# mother_board.net
KiCad netlist of a schematic drawn in EAGLE
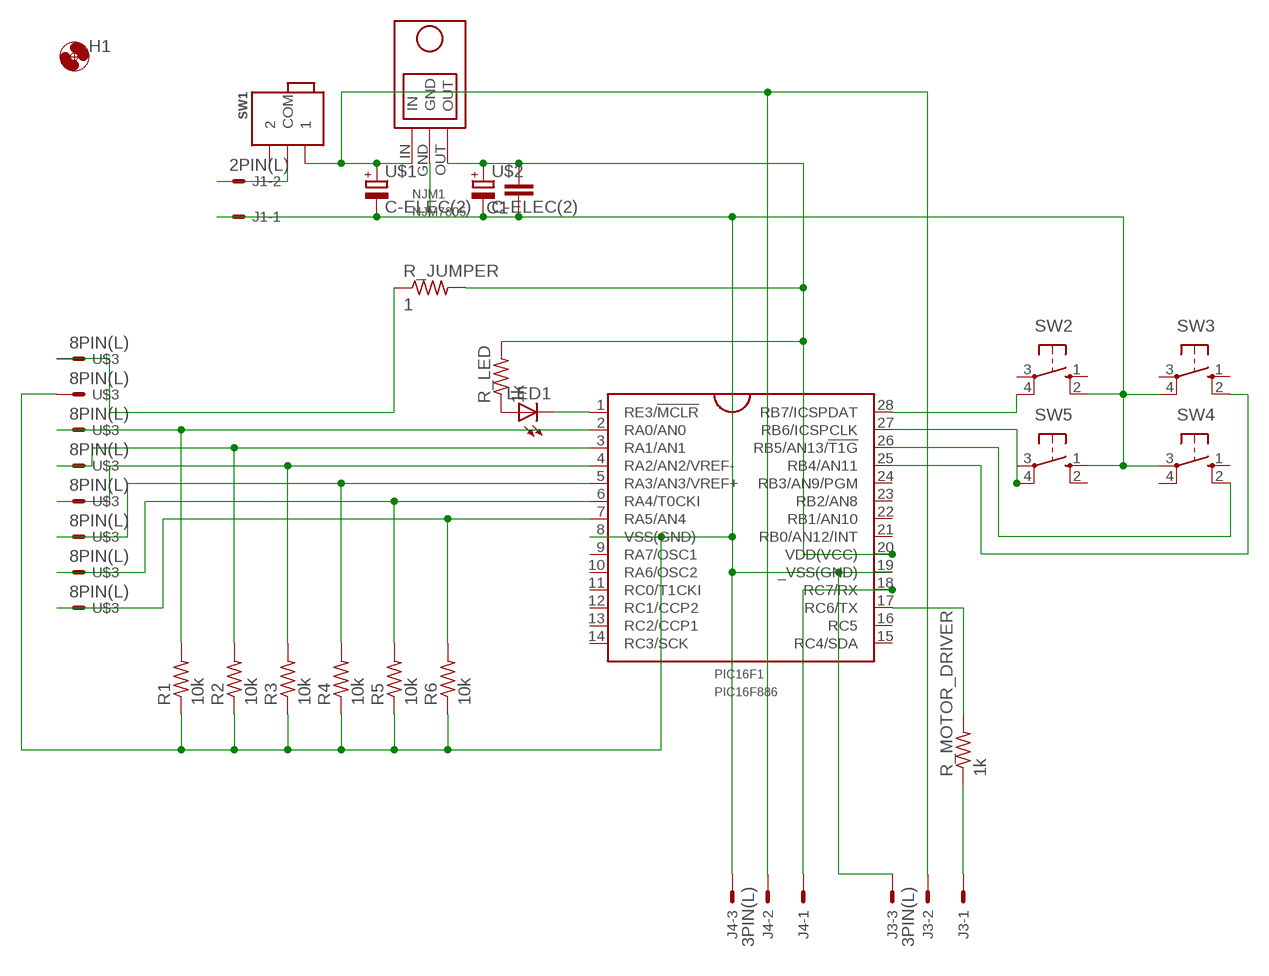
[diagram p0: schematic, sheet 1]

(export (version "E")
  (design (tool "Eeschema 10.0.6"))
  (components
    (comp (ref "C1")
      (value "C-3")
      (footprint "eagle-import:C-3")
      (libsource (lib "eagle-import") (part "C-3"))
    )
    (comp (ref "H1")
      (value "HOLE3.3M3BOLT")
      (footprint "eagle-import:HOLE3.3")
      (libsource (lib "eagle-import") (part "HOLE3.3M3BOLT"))
    )
    (comp (ref "J1")
      (value "2PIN(L)")
      (footprint "eagle-import:2PL")
      (libsource (lib "eagle-import") (part "2PIN(L)"))
    )
    (comp (ref "J3")
      (value "3PIN(L)")
      (footprint "eagle-import:3PL")
      (libsource (lib "eagle-import") (part "3PIN(L)"))
    )
    (comp (ref "J4")
      (value "3PIN(L)")
      (footprint "eagle-import:3PL")
      (libsource (lib "eagle-import") (part "3PIN(L)"))
    )
    (comp (ref "LED1")
      (value "LED-2")
      (footprint "eagle-import:LED5MM-2")
      (libsource (lib "eagle-import") (part "LED-2"))
    )
    (comp (ref "NJM1")
      (value "NJM7805")
      (footprint "eagle-import:NJM7805")
      (libsource (lib "eagle-import") (part "NJM7805"))
    )
    (comp (ref "PIC16F1")
      (value "PIC16F886")
      (footprint "eagle-import:DIL28-3")
      (libsource (lib "eagle-import") (part "PIC16F886"))
    )
    (comp (ref "R1")
      (value "10k")
      (footprint "eagle-import:0207_10")
      (libsource (lib "eagle-import") (part "R-"))
    )
    (comp (ref "R2")
      (value "10k")
      (footprint "eagle-import:0207_10")
      (libsource (lib "eagle-import") (part "R-"))
    )
    (comp (ref "R3")
      (value "10k")
      (footprint "eagle-import:0207_10")
      (libsource (lib "eagle-import") (part "R-"))
    )
    (comp (ref "R4")
      (value "10k")
      (footprint "eagle-import:0207_10")
      (libsource (lib "eagle-import") (part "R-"))
    )
    (comp (ref "R5")
      (value "10k")
      (footprint "eagle-import:0207_10")
      (libsource (lib "eagle-import") (part "R-"))
    )
    (comp (ref "R6")
      (value "10k")
      (footprint "eagle-import:0207_10")
      (libsource (lib "eagle-import") (part "R-"))
    )
    (comp (ref "R_JUMPER")
      (value "1")
      (footprint "eagle-import:0207_10")
      (libsource (lib "eagle-import") (part "R-"))
    )
    (comp (ref "R_LED")
      (value "1k")
      (footprint "eagle-import:0207_10")
      (libsource (lib "eagle-import") (part "R-"))
    )
    (comp (ref "R_MOTOR_DRIVER")
      (value "1k")
      (footprint "eagle-import:0207_10")
      (libsource (lib "eagle-import") (part "R-"))
    )
    (comp (ref "SW1")
      (value "SWITCH_MININORMAL")
      (footprint "eagle-import:SWITCH_MINI")
      (libsource (lib "eagle-import") (part "SWITCH_MININORMAL"))
    )
    (comp (ref "SW2")
      (value "TACTSW")
      (footprint "eagle-import:TACT")
      (libsource (lib "eagle-import") (part "TACTSW"))
    )
    (comp (ref "SW3")
      (value "TACTSW")
      (footprint "eagle-import:TACT")
      (libsource (lib "eagle-import") (part "TACTSW"))
    )
    (comp (ref "SW4")
      (value "TACTSW")
      (footprint "eagle-import:TACT")
      (libsource (lib "eagle-import") (part "TACTSW"))
    )
    (comp (ref "SW5")
      (value "TACTSW")
      (footprint "eagle-import:TACT")
      (libsource (lib "eagle-import") (part "TACTSW"))
    )
    (comp (ref "U$1")
      (value "C-ELEC(2)")
      (footprint "eagle-import:C-6MM(2)")
      (libsource (lib "eagle-import") (part "C-ELEC(2)"))
    )
    (comp (ref "U$2")
      (value "C-ELEC(2)")
      (footprint "eagle-import:C-6MM(2)")
      (libsource (lib "eagle-import") (part "C-ELEC(2)"))
    )
    (comp (ref "U$3")
      (value "8PIN(L)")
      (footprint "eagle-import:8PL")
      (libsource (lib "eagle-import") (part "8PIN(L)"))
    )
  )
  (nets
    (net (code "1") (name "/9V") (class "Default")
      (node (ref "J1") (pin "2") (pinfunction "S_2") (pintype "passive"))
      (node (ref "J3") (pin "2") (pinfunction "S_2") (pintype "passive"))
      (node (ref "J4") (pin "2") (pinfunction "S_2") (pintype "passive"))
      (node (ref "NJM1") (pin "IN") (pinfunction "IN_IN") (pintype "bidirectional"))
      (node (ref "SW1") (pin "1") (pinfunction "1_1") (pintype "passive"))
      (node (ref "SW1") (pin "COM") (pinfunction "COM_COM") (pintype "passive"))
      (node (ref "U$1") (pin "+") (pinfunction "+_+") (pintype "passive"))
    )
    (net (code "2") (name "Net-(J1A-S)") (class "Default")
      (node (ref "C1") (pin "1") (pinfunction "1_1") (pintype "passive"))
      (node (ref "J1") (pin "1") (pinfunction "S_1") (pintype "passive"))
      (node (ref "J3") (pin "3") (pinfunction "S_3") (pintype "passive"))
      (node (ref "J4") (pin "3") (pinfunction "S_3") (pintype "passive"))
      (node (ref "NJM1") (pin "GND") (pinfunction "GND_GND") (pintype "bidirectional"))
      (node (ref "PIC16F1") (pin "19") (pinfunction "_VSS(GND)_19") (pintype "power_in"))
      (node (ref "PIC16F1") (pin "8") (pinfunction "VSS(GND)_8") (pintype "power_in"))
      (node (ref "R1") (pin "1") (pinfunction "1_1") (pintype "passive"))
      (node (ref "R2") (pin "1") (pinfunction "1_1") (pintype "passive"))
      (node (ref "R3") (pin "1") (pinfunction "1_1") (pintype "passive"))
      (node (ref "R4") (pin "1") (pinfunction "1_1") (pintype "passive"))
      (node (ref "R5") (pin "1") (pinfunction "1_1") (pintype "passive"))
      (node (ref "R6") (pin "1") (pinfunction "1_1") (pintype "passive"))
      (node (ref "SW2") (pin "2") (pinfunction "S1_2") (pintype "passive"))
      (node (ref "SW3") (pin "4") (pinfunction "P1_4") (pintype "passive"))
      (node (ref "SW4") (pin "3") (pinfunction "P_3") (pintype "passive"))
      (node (ref "SW5") (pin "1") (pinfunction "S_1") (pintype "passive"))
      (node (ref "U$1") (pin "-") (pinfunction "-_-") (pintype "passive"))
      (node (ref "U$2") (pin "-") (pinfunction "-_-") (pintype "passive"))
      (node (ref "U$3") (pin "P7") (pinfunction "P7_P7") (pintype "passive"))
    )
    (net (code "3") (name "Net-(J3A-S)") (class "Default")
      (node (ref "J3") (pin "1") (pinfunction "S_1") (pintype "passive"))
      (node (ref "R_MOTOR_DRIVER") (pin "1") (pinfunction "1_1") (pintype "passive"))
    )
    (net (code "4") (name "Net-(J4A-S)") (class "Default")
      (node (ref "J4") (pin "1") (pinfunction "S_1") (pintype "passive"))
      (node (ref "PIC16F1") (pin "18") (pinfunction "RC7/RX_18") (pintype "bidirectional"))
    )
    (net (code "5") (name "Net-(LED1-C)") (class "Default")
      (node (ref "LED1") (pin "K") (pinfunction "C_K") (pintype "passive"))
      (node (ref "PIC16F1") (pin "1") (pinfunction "RE3/~{MCLR}_1") (pintype "bidirectional"))
    )
    (net (code "6") (name "Net-(LED1-PadA)") (class "Default")
      (node (ref "LED1") (pin "A") (pinfunction "A_A") (pintype "passive"))
      (node (ref "R_LED") (pin "1") (pinfunction "1_1") (pintype "passive"))
    )
    (net (code "7") (name "Net-(PIC16F1-RA0{slash}AN0)") (class "Default")
      (node (ref "PIC16F1") (pin "2") (pinfunction "RA0/AN0_2") (pintype "bidirectional"))
      (node (ref "R1") (pin "2") (pinfunction "2_2") (pintype "passive"))
      (node (ref "U$3") (pin "P6") (pinfunction "P6_P6") (pintype "passive"))
    )
    (net (code "8") (name "Net-(PIC16F1-RA1{slash}AN1)") (class "Default")
      (node (ref "PIC16F1") (pin "3") (pinfunction "RA1/AN1_3") (pintype "bidirectional"))
      (node (ref "R2") (pin "2") (pinfunction "2_2") (pintype "passive"))
      (node (ref "U$3") (pin "P5") (pinfunction "P5_P5") (pintype "passive"))
    )
    (net (code "9") (name "Net-(PIC16F1-RA2{slash}AN2{slash}VREF-)") (class "Default")
      (node (ref "PIC16F1") (pin "4") (pinfunction "RA2/AN2/VREF-_4") (pintype "bidirectional"))
      (node (ref "R3") (pin "2") (pinfunction "2_2") (pintype "passive"))
      (node (ref "U$3") (pin "P4") (pinfunction "P4_P4") (pintype "passive"))
    )
    (net (code "10") (name "Net-(PIC16F1-RA3{slash}AN3{slash}VREF+)") (class "Default")
      (node (ref "PIC16F1") (pin "5") (pinfunction "RA3/AN3/VREF+_5") (pintype "bidirectional"))
      (node (ref "R4") (pin "2") (pinfunction "2_2") (pintype "passive"))
      (node (ref "U$3") (pin "P3") (pinfunction "P3_P3") (pintype "passive"))
    )
    (net (code "11") (name "Net-(PIC16F1-RA4{slash}T0CKI)") (class "Default")
      (node (ref "PIC16F1") (pin "6") (pinfunction "RA4/T0CKI_6") (pintype "bidirectional"))
      (node (ref "R5") (pin "2") (pinfunction "2_2") (pintype "passive"))
      (node (ref "U$3") (pin "P2") (pinfunction "P2_P2") (pintype "passive"))
    )
    (net (code "12") (name "Net-(PIC16F1-RA5{slash}AN4)") (class "Default")
      (node (ref "PIC16F1") (pin "7") (pinfunction "RA5/AN4_7") (pintype "bidirectional"))
      (node (ref "R6") (pin "2") (pinfunction "2_2") (pintype "passive"))
      (node (ref "U$3") (pin "P1") (pinfunction "P1_P1") (pintype "passive"))
    )
    (net (code "13") (name "Net-(PIC16F1-RB4{slash}AN11)") (class "Default")
      (node (ref "PIC16F1") (pin "25") (pinfunction "RB4/AN11_25") (pintype "bidirectional"))
      (node (ref "SW3") (pin "2") (pinfunction "S1_2") (pintype "passive"))
    )
    (net (code "14") (name "Net-(PIC16F1-RB5{slash}AN13{slash}~{T1G})") (class "Default")
      (node (ref "PIC16F1") (pin "26") (pinfunction "RB5/AN13/~{T1G}_26") (pintype "bidirectional"))
      (node (ref "SW4") (pin "2") (pinfunction "S1_2") (pintype "passive"))
    )
    (net (code "15") (name "Net-(PIC16F1-RB6{slash}ICSPCLK)") (class "Default")
      (node (ref "PIC16F1") (pin "27") (pinfunction "RB6/ICSPCLK_27") (pintype "bidirectional"))
      (node (ref "SW5") (pin "4") (pinfunction "P1_4") (pintype "passive"))
    )
    (net (code "16") (name "Net-(PIC16F1-RB7{slash}ICSPDAT)") (class "Default")
      (node (ref "PIC16F1") (pin "28") (pinfunction "RB7/ICSPDAT_28") (pintype "bidirectional"))
      (node (ref "SW2") (pin "4") (pinfunction "P1_4") (pintype "passive"))
    )
    (net (code "17") (name "Net-(PIC16F1-RC6{slash}TX)") (class "Default")
      (node (ref "PIC16F1") (pin "17") (pinfunction "RC6/TX_17") (pintype "bidirectional"))
      (node (ref "R_MOTOR_DRIVER") (pin "2") (pinfunction "2_2") (pintype "passive"))
    )
    (net (code "18") (name "Net-(PIC16F1-VDD(VCC))") (class "Default")
      (node (ref "C1") (pin "2") (pinfunction "2_2") (pintype "passive"))
      (node (ref "NJM1") (pin "OUT") (pinfunction "OUT_OUT") (pintype "bidirectional"))
      (node (ref "PIC16F1") (pin "20") (pinfunction "VDD(VCC)_20") (pintype "power_in"))
      (node (ref "R_JUMPER") (pin "2") (pinfunction "2_2") (pintype "passive"))
      (node (ref "R_LED") (pin "2") (pinfunction "2_2") (pintype "passive"))
      (node (ref "U$2") (pin "+") (pinfunction "+_+") (pintype "passive"))
    )
    (net (code "19") (name "Net-(R_JUMPER-Pad1)") (class "Default")
      (node (ref "R_JUMPER") (pin "1") (pinfunction "1_1") (pintype "passive"))
      (node (ref "U$3") (pin "P8") (pinfunction "P8_P8") (pintype "passive"))
    )
    (net (code "20") (name "unconnected-(PIC16F1-RA6{slash}OSC2-Pad10)") (class "Default")
      (node (ref "PIC16F1") (pin "10") (pinfunction "RA6/OSC2_10") (pintype "bidirectional"))
    )
    (net (code "21") (name "unconnected-(PIC16F1-RA7{slash}OSC1-Pad9)") (class "Default")
      (node (ref "PIC16F1") (pin "9") (pinfunction "RA7/OSC1_9") (pintype "bidirectional"))
    )
    (net (code "22") (name "unconnected-(PIC16F1-RB0{slash}AN12{slash}INT-Pad21)") (class "Default")
      (node (ref "PIC16F1") (pin "21") (pinfunction "RB0/AN12/INT_21") (pintype "bidirectional"))
    )
    (net (code "23") (name "unconnected-(PIC16F1-RB1{slash}AN10-Pad22)") (class "Default")
      (node (ref "PIC16F1") (pin "22") (pinfunction "RB1/AN10_22") (pintype "bidirectional"))
    )
    (net (code "24") (name "unconnected-(PIC16F1-RB2{slash}AN8-Pad23)") (class "Default")
      (node (ref "PIC16F1") (pin "23") (pinfunction "RB2/AN8_23") (pintype "bidirectional"))
    )
    (net (code "25") (name "unconnected-(PIC16F1-RB3{slash}AN9{slash}PGM-Pad24)") (class "Default")
      (node (ref "PIC16F1") (pin "24") (pinfunction "RB3/AN9/PGM_24") (pintype "bidirectional"))
    )
    (net (code "26") (name "unconnected-(PIC16F1-RC0{slash}T1CKI-Pad11)") (class "Default")
      (node (ref "PIC16F1") (pin "11") (pinfunction "RC0/T1CKI_11") (pintype "bidirectional"))
    )
    (net (code "27") (name "unconnected-(PIC16F1-RC1{slash}CCP2-Pad12)") (class "Default")
      (node (ref "PIC16F1") (pin "12") (pinfunction "RC1/CCP2_12") (pintype "bidirectional"))
    )
    (net (code "28") (name "unconnected-(PIC16F1-RC2{slash}CCP1-Pad13)") (class "Default")
      (node (ref "PIC16F1") (pin "13") (pinfunction "RC2/CCP1_13") (pintype "bidirectional"))
    )
    (net (code "29") (name "unconnected-(PIC16F1-RC3{slash}SCK-Pad14)") (class "Default")
      (node (ref "PIC16F1") (pin "14") (pinfunction "RC3/SCK_14") (pintype "bidirectional"))
    )
    (net (code "30") (name "unconnected-(PIC16F1-RC4{slash}SDA-Pad15)") (class "Default")
      (node (ref "PIC16F1") (pin "15") (pinfunction "RC4/SDA_15") (pintype "bidirectional"))
    )
    (net (code "31") (name "unconnected-(PIC16F1-RC5-Pad16)") (class "Default")
      (node (ref "PIC16F1") (pin "16") (pinfunction "RC5_16") (pintype "bidirectional"))
    )
    (net (code "32") (name "unconnected-(SW1-Pad2)") (class "Default")
      (node (ref "SW1") (pin "2") (pinfunction "2_2") (pintype "no_connect"))
    )
    (net (code "33") (name "unconnected-(SW2-P-Pad3)") (class "Default")
      (node (ref "SW2") (pin "3") (pinfunction "P_3") (pintype "passive"))
    )
    (net (code "34") (name "unconnected-(SW2-S-Pad1)") (class "Default")
      (node (ref "SW2") (pin "1") (pinfunction "S_1") (pintype "passive"))
    )
    (net (code "35") (name "unconnected-(SW3-P-Pad3)") (class "Default")
      (node (ref "SW3") (pin "3") (pinfunction "P_3") (pintype "passive"))
    )
    (net (code "36") (name "unconnected-(SW3-S-Pad1)") (class "Default")
      (node (ref "SW3") (pin "1") (pinfunction "S_1") (pintype "passive"))
    )
    (net (code "37") (name "unconnected-(SW4-P1-Pad4)") (class "Default")
      (node (ref "SW4") (pin "4") (pinfunction "P1_4") (pintype "passive"))
    )
    (net (code "38") (name "unconnected-(SW4-S-Pad1)") (class "Default")
      (node (ref "SW4") (pin "1") (pinfunction "S_1") (pintype "passive"))
    )
    (net (code "39") (name "unconnected-(SW5-P-Pad3)") (class "Default")
      (node (ref "SW5") (pin "3") (pinfunction "P_3") (pintype "passive"))
    )
    (net (code "40") (name "unconnected-(SW5-S1-Pad2)") (class "Default")
      (node (ref "SW5") (pin "2") (pinfunction "S1_2") (pintype "passive"))
    )
  )
)
